# DIY_tool_-_Arduino_nano_shield_v1_1.net
KiCad netlist of a schematic drawn in EAGLE
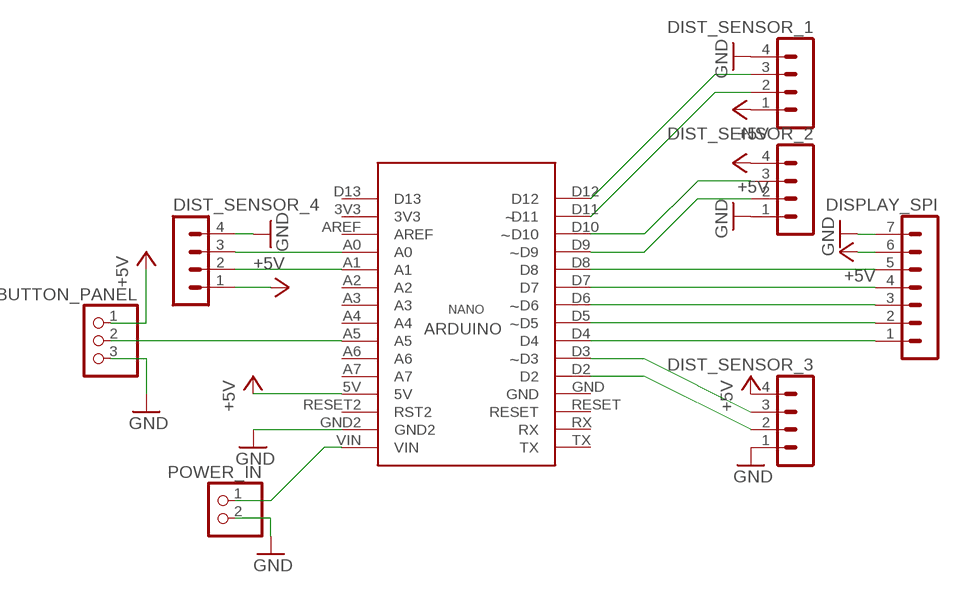
[diagram p0: schematic, sheet 1]

(export (version "E")
  (design (tool "Eeschema 10.0.6"))
  (components
    (comp (ref "BUTTON_PANEL")
      (value "PINHD-1X3")
      (footprint "eagle-import:1X03")
      (libsource (lib "eagle-import") (part "PINHD-1X3"))
    )
    (comp (ref "DISPLAY_SPI")
      (value "MA07-1")
      (footprint "eagle-import:MA07-1")
      (libsource (lib "eagle-import") (part "MA07-1"))
    )
    (comp (ref "DIST_SENSOR_1")
      (value "MA04-1")
      (footprint "eagle-import:MA04-1")
      (libsource (lib "eagle-import") (part "MA04-1"))
    )
    (comp (ref "DIST_SENSOR_2")
      (value "MA04-1")
      (footprint "eagle-import:MA04-1")
      (libsource (lib "eagle-import") (part "MA04-1"))
    )
    (comp (ref "DIST_SENSOR_3")
      (value "MA04-1")
      (footprint "eagle-import:MA04-1")
      (libsource (lib "eagle-import") (part "MA04-1"))
    )
    (comp (ref "DIST_SENSOR_4")
      (value "MA04-1")
      (footprint "eagle-import:MA04-1")
      (libsource (lib "eagle-import") (part "MA04-1"))
    )
    (comp (ref "POWER_IN")
      (value "PINHD-1X2")
      (footprint "eagle-import:1X02")
      (libsource (lib "eagle-import") (part "PINHD-1X2"))
    )
    (comp (ref "U$2")
      (value "NANO")
      (footprint "eagle-import:NANO")
      (libsource (lib "eagle-import") (part "NANO"))
    )
  )
  (nets
    (net (code "1") (name "+5V") (class "Default")
      (node (ref "BUTTON_PANEL") (pin "1") (pinfunction "1_1") (pintype "passive"))
      (node (ref "DISPLAY_SPI") (pin "6") (pinfunction "6_6") (pintype "passive"))
      (node (ref "DIST_SENSOR_1") (pin "1") (pinfunction "1_1") (pintype "passive"))
      (node (ref "DIST_SENSOR_2") (pin "4") (pinfunction "4_4") (pintype "passive"))
      (node (ref "DIST_SENSOR_3") (pin "4") (pinfunction "4_4") (pintype "passive"))
      (node (ref "DIST_SENSOR_4") (pin "1") (pinfunction "1_1") (pintype "passive"))
      (node (ref "U$2") (pin "5V") (pinfunction "5V_5V") (pintype "bidirectional"))
    )
    (net (code "2") (name "GND") (class "Default")
      (node (ref "BUTTON_PANEL") (pin "3") (pinfunction "3_3") (pintype "passive"))
      (node (ref "DISPLAY_SPI") (pin "7") (pinfunction "7_7") (pintype "passive"))
      (node (ref "DIST_SENSOR_1") (pin "4") (pinfunction "4_4") (pintype "passive"))
      (node (ref "DIST_SENSOR_2") (pin "1") (pinfunction "1_1") (pintype "passive"))
      (node (ref "DIST_SENSOR_3") (pin "1") (pinfunction "1_1") (pintype "passive"))
      (node (ref "DIST_SENSOR_4") (pin "4") (pinfunction "4_4") (pintype "passive"))
      (node (ref "POWER_IN") (pin "2") (pinfunction "2_2") (pintype "passive"))
      (node (ref "U$2") (pin "GND2") (pinfunction "GND2_GND2") (pintype "bidirectional"))
    )
    (net (code "3") (name "Net-(BUTTON_PANEL-Pad2)") (class "Default")
      (node (ref "BUTTON_PANEL") (pin "2") (pinfunction "2_2") (pintype "passive"))
      (node (ref "U$2") (pin "A5") (pinfunction "A5_A5") (pintype "bidirectional"))
    )
    (net (code "4") (name "Net-(DISPLAY_SPI-Pad1)") (class "Default")
      (node (ref "DISPLAY_SPI") (pin "1") (pinfunction "1_1") (pintype "passive"))
      (node (ref "U$2") (pin "D4") (pinfunction "D4_D4") (pintype "bidirectional"))
    )
    (net (code "5") (name "Net-(DISPLAY_SPI-Pad2)") (class "Default")
      (node (ref "DISPLAY_SPI") (pin "2") (pinfunction "2_2") (pintype "passive"))
      (node (ref "U$2") (pin "D5") (pinfunction "D5_D5") (pintype "bidirectional"))
    )
    (net (code "6") (name "Net-(DISPLAY_SPI-Pad3)") (class "Default")
      (node (ref "DISPLAY_SPI") (pin "3") (pinfunction "3_3") (pintype "passive"))
      (node (ref "U$2") (pin "D6") (pinfunction "D6_D6") (pintype "bidirectional"))
    )
    (net (code "7") (name "Net-(DISPLAY_SPI-Pad4)") (class "Default")
      (node (ref "DISPLAY_SPI") (pin "4") (pinfunction "4_4") (pintype "passive"))
      (node (ref "U$2") (pin "D7") (pinfunction "D7_D7") (pintype "bidirectional"))
    )
    (net (code "8") (name "Net-(DISPLAY_SPI-Pad5)") (class "Default")
      (node (ref "DISPLAY_SPI") (pin "5") (pinfunction "5_5") (pintype "passive"))
      (node (ref "U$2") (pin "D8") (pinfunction "D8_D8") (pintype "bidirectional"))
    )
    (net (code "9") (name "Net-(DIST_SENSOR_1-Pad2)") (class "Default")
      (node (ref "DIST_SENSOR_1") (pin "2") (pinfunction "2_2") (pintype "passive"))
      (node (ref "U$2") (pin "D11") (pinfunction "D11_D11") (pintype "bidirectional"))
    )
    (net (code "10") (name "Net-(DIST_SENSOR_1-Pad3)") (class "Default")
      (node (ref "DIST_SENSOR_1") (pin "3") (pinfunction "3_3") (pintype "passive"))
      (node (ref "U$2") (pin "D12") (pinfunction "D12_D12") (pintype "bidirectional"))
    )
    (net (code "11") (name "Net-(DIST_SENSOR_2-Pad2)") (class "Default")
      (node (ref "DIST_SENSOR_2") (pin "2") (pinfunction "2_2") (pintype "passive"))
      (node (ref "U$2") (pin "D9") (pinfunction "D9_D9") (pintype "bidirectional"))
    )
    (net (code "12") (name "Net-(DIST_SENSOR_2-Pad3)") (class "Default")
      (node (ref "DIST_SENSOR_2") (pin "3") (pinfunction "3_3") (pintype "passive"))
      (node (ref "U$2") (pin "D10") (pinfunction "D10_D10") (pintype "bidirectional"))
    )
    (net (code "13") (name "Net-(DIST_SENSOR_3-Pad2)") (class "Default")
      (node (ref "DIST_SENSOR_3") (pin "2") (pinfunction "2_2") (pintype "passive"))
      (node (ref "U$2") (pin "D2") (pinfunction "D2_D2") (pintype "bidirectional"))
    )
    (net (code "14") (name "Net-(DIST_SENSOR_3-Pad3)") (class "Default")
      (node (ref "DIST_SENSOR_3") (pin "3") (pinfunction "3_3") (pintype "passive"))
      (node (ref "U$2") (pin "D3") (pinfunction "D3_D3") (pintype "bidirectional"))
    )
    (net (code "15") (name "Net-(DIST_SENSOR_4-Pad2)") (class "Default")
      (node (ref "DIST_SENSOR_4") (pin "2") (pinfunction "2_2") (pintype "passive"))
      (node (ref "U$2") (pin "A1") (pinfunction "A1_A1") (pintype "bidirectional"))
    )
    (net (code "16") (name "Net-(DIST_SENSOR_4-Pad3)") (class "Default")
      (node (ref "DIST_SENSOR_4") (pin "3") (pinfunction "3_3") (pintype "passive"))
      (node (ref "U$2") (pin "A0") (pinfunction "A0_A0") (pintype "bidirectional"))
    )
    (net (code "17") (name "Net-(POWER_IN-Pad1)") (class "Default")
      (node (ref "POWER_IN") (pin "1") (pinfunction "1_1") (pintype "passive"))
      (node (ref "U$2") (pin "VIN") (pinfunction "VIN_VIN") (pintype "bidirectional"))
    )
    (net (code "18") (name "unconnected-(U$2-Pad3V3)") (class "Default")
      (node (ref "U$2") (pin "3V3") (pinfunction "3V3_3V3") (pintype "bidirectional"))
    )
    (net (code "19") (name "unconnected-(U$2-PadA2)") (class "Default")
      (node (ref "U$2") (pin "A2") (pinfunction "A2_A2") (pintype "bidirectional"))
    )
    (net (code "20") (name "unconnected-(U$2-PadA3)") (class "Default")
      (node (ref "U$2") (pin "A3") (pinfunction "A3_A3") (pintype "bidirectional"))
    )
    (net (code "21") (name "unconnected-(U$2-PadA4)") (class "Default")
      (node (ref "U$2") (pin "A4") (pinfunction "A4_A4") (pintype "bidirectional"))
    )
    (net (code "22") (name "unconnected-(U$2-PadA6)") (class "Default")
      (node (ref "U$2") (pin "A6") (pinfunction "A6_A6") (pintype "bidirectional"))
    )
    (net (code "23") (name "unconnected-(U$2-PadA7)") (class "Default")
      (node (ref "U$2") (pin "A7") (pinfunction "A7_A7") (pintype "bidirectional"))
    )
    (net (code "24") (name "unconnected-(U$2-PadAREF)") (class "Default")
      (node (ref "U$2") (pin "AREF") (pinfunction "AREF_AREF") (pintype "bidirectional"))
    )
    (net (code "25") (name "unconnected-(U$2-PadD13)") (class "Default")
      (node (ref "U$2") (pin "D13") (pinfunction "D13_D13") (pintype "bidirectional"))
    )
    (net (code "26") (name "unconnected-(U$2-PadGND)") (class "Default")
      (node (ref "U$2") (pin "GND") (pinfunction "GND_GND") (pintype "bidirectional"))
    )
    (net (code "27") (name "unconnected-(U$2-PadRESET)") (class "Default")
      (node (ref "U$2") (pin "RESET") (pinfunction "RESET_RESET") (pintype "bidirectional"))
    )
    (net (code "28") (name "unconnected-(U$2-PadRX)") (class "Default")
      (node (ref "U$2") (pin "RX") (pinfunction "RX_RX") (pintype "bidirectional"))
    )
    (net (code "29") (name "unconnected-(U$2-PadTX)") (class "Default")
      (node (ref "U$2") (pin "TX") (pinfunction "TX_TX") (pintype "bidirectional"))
    )
    (net (code "30") (name "unconnected-(U$2-RST2-PadRESET2)") (class "Default")
      (node (ref "U$2") (pin "RESET2") (pinfunction "RST2_RESET2") (pintype "bidirectional"))
    )
  )
)
